# schematic.net
KiCad netlist of a schematic drawn in EAGLE
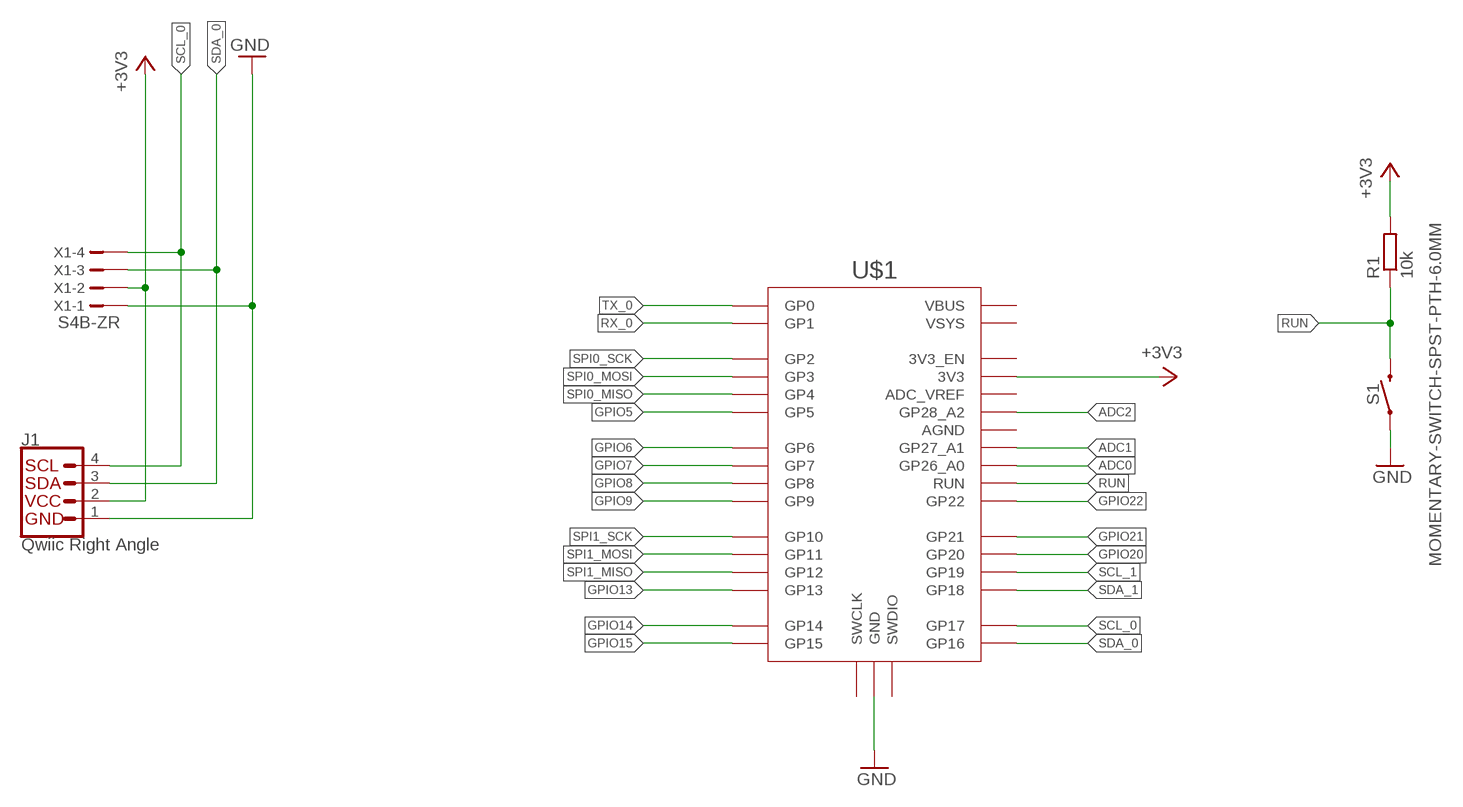
[diagram p0: schematic, sheet 1]

(export (version "E")
  (design (tool "Eeschema 10.0.6"))
  (components
    (comp (ref "J1")
      (value "Qwiic Right Angle")
      (footprint "eagle-import:JST04_1MM_RA")
      (libsource (lib "eagle-import") (part "I2C_STANDARDQWIIC"))
    )
    (comp (ref "R1")
      (value "10k")
      (footprint "eagle-import:0204_7")
      (libsource (lib "eagle-import") (part "R-EU_0204/7"))
    )
    (comp (ref "S1")
      (value "MOMENTARY-SWITCH-SPST-PTH-6.0MM")
      (footprint "eagle-import:TACTILE_SWITCH_PTH_6.0MM")
      (libsource (lib "eagle-import") (part "MOMENTARY-SWITCH-SPST-PTH-6.0MM"))
    )
    (comp (ref "U$1")
      (value "RPI_PICO-SMD")
      (footprint "eagle-import:RPI_PICO")
      (libsource (lib "eagle-import") (part "RPI_PICO-SMD"))
    )
    (comp (ref "X1")
      (value "S4B-ZR")
      (footprint "eagle-import:S4B-ZR")
      (fields (field (name "MF") "FARNELL") (field (name "MPN") "S4B-ZR(LF)(SN)"))
      (libsource (lib "eagle-import") (part "?4B-ZRS"))
    )
  )
  (nets
    (net (code "1") (name "+3V3") (class "Default")
      (node (ref "J1") (pin "2") (pinfunction "2_2") (pintype "power_in"))
      (node (ref "R1") (pin "2") (pinfunction "2_2") (pintype "passive"))
      (node (ref "U$1") (pin "3V3") (pinfunction "3V3_3V3") (pintype "bidirectional"))
      (node (ref "X1") (pin "2") (pinfunction "1_2") (pintype "passive"))
    )
    (net (code "2") (name "ADC0") (class "Default")
      (node (ref "U$1") (pin "GP26_A0") (pinfunction "GP26_A0_GP26_A0") (pintype "bidirectional"))
    )
    (net (code "3") (name "ADC1") (class "Default")
      (node (ref "U$1") (pin "GP27_A1") (pinfunction "GP27_A1_GP27_A1") (pintype "bidirectional"))
    )
    (net (code "4") (name "ADC2") (class "Default")
      (node (ref "U$1") (pin "GP28_A2") (pinfunction "GP28_A2_GP28_A2") (pintype "bidirectional"))
    )
    (net (code "5") (name "GND") (class "Default")
      (node (ref "J1") (pin "1") (pinfunction "1_1") (pintype "power_in"))
      (node (ref "S1") (pin "1") (pinfunction "1_1") (pintype "passive"))
      (node (ref "U$1") (pin "GND@1") (pinfunction "GND_GND@1") (pintype "bidirectional"))
      (node (ref "U$1") (pin "GND@2") (pinfunction "GND_GND@2") (pintype "bidirectional"))
      (node (ref "U$1") (pin "GND@3") (pinfunction "GND_GND@3") (pintype "bidirectional"))
      (node (ref "U$1") (pin "GND@4") (pinfunction "GND_GND@4") (pintype "bidirectional"))
      (node (ref "U$1") (pin "GND@5") (pinfunction "GND_GND@5") (pintype "bidirectional"))
      (node (ref "U$1") (pin "GND@6") (pinfunction "GND_GND@6") (pintype "bidirectional"))
      (node (ref "U$1") (pin "GND@7") (pinfunction "GND_GND@7") (pintype "bidirectional"))
      (node (ref "U$1") (pin "GND@8") (pinfunction "GND_GND@8") (pintype "bidirectional"))
      (node (ref "X1") (pin "1") (pinfunction "1_1") (pintype "passive"))
    )
    (net (code "6") (name "GPIO5") (class "Default")
      (node (ref "U$1") (pin "GP5") (pinfunction "GP5_GP5") (pintype "bidirectional"))
    )
    (net (code "7") (name "GPIO6") (class "Default")
      (node (ref "U$1") (pin "GP6") (pinfunction "GP6_GP6") (pintype "bidirectional"))
    )
    (net (code "8") (name "GPIO7") (class "Default")
      (node (ref "U$1") (pin "GP7") (pinfunction "GP7_GP7") (pintype "bidirectional"))
    )
    (net (code "9") (name "GPIO8") (class "Default")
      (node (ref "U$1") (pin "GP8") (pinfunction "GP8_GP8") (pintype "bidirectional"))
    )
    (net (code "10") (name "GPIO9") (class "Default")
      (node (ref "U$1") (pin "GP9") (pinfunction "GP9_GP9") (pintype "bidirectional"))
    )
    (net (code "11") (name "GPIO13") (class "Default")
      (node (ref "U$1") (pin "GP13") (pinfunction "GP13_GP13") (pintype "bidirectional"))
    )
    (net (code "12") (name "GPIO14") (class "Default")
      (node (ref "U$1") (pin "GP14") (pinfunction "GP14_GP14") (pintype "bidirectional"))
    )
    (net (code "13") (name "GPIO15") (class "Default")
      (node (ref "U$1") (pin "GP15") (pinfunction "GP15_GP15") (pintype "bidirectional"))
    )
    (net (code "14") (name "GPIO20") (class "Default")
      (node (ref "U$1") (pin "GP20") (pinfunction "GP20_GP20") (pintype "bidirectional"))
    )
    (net (code "15") (name "GPIO21") (class "Default")
      (node (ref "U$1") (pin "GP21") (pinfunction "GP21_GP21") (pintype "bidirectional"))
    )
    (net (code "16") (name "GPIO22") (class "Default")
      (node (ref "U$1") (pin "GP22") (pinfunction "GP22_GP22") (pintype "bidirectional"))
    )
    (net (code "17") (name "RUN") (class "Default")
      (node (ref "R1") (pin "1") (pinfunction "1_1") (pintype "passive"))
      (node (ref "S1") (pin "3") (pinfunction "2_3") (pintype "passive"))
      (node (ref "U$1") (pin "RUN") (pinfunction "RUN_RUN") (pintype "bidirectional"))
    )
    (net (code "18") (name "RX_0") (class "Default")
      (node (ref "U$1") (pin "GP1") (pinfunction "GP1_GP1") (pintype "bidirectional"))
    )
    (net (code "19") (name "SCL_0") (class "Default")
      (node (ref "J1") (pin "4") (pinfunction "4_4") (pintype "passive"))
      (node (ref "U$1") (pin "GP17") (pinfunction "GP17_GP17") (pintype "bidirectional"))
      (node (ref "X1") (pin "4") (pinfunction "1_4") (pintype "passive"))
    )
    (net (code "20") (name "SCL_1") (class "Default")
      (node (ref "U$1") (pin "GP19") (pinfunction "GP19_GP19") (pintype "bidirectional"))
    )
    (net (code "21") (name "SDA_0") (class "Default")
      (node (ref "J1") (pin "3") (pinfunction "3_3") (pintype "passive"))
      (node (ref "U$1") (pin "GP16") (pinfunction "GP16_GP16") (pintype "bidirectional"))
      (node (ref "X1") (pin "3") (pinfunction "1_3") (pintype "passive"))
    )
    (net (code "22") (name "SDA_1") (class "Default")
      (node (ref "U$1") (pin "GP18") (pinfunction "GP18_GP18") (pintype "bidirectional"))
    )
    (net (code "23") (name "SPI0_MISO") (class "Default")
      (node (ref "U$1") (pin "GP4") (pinfunction "GP4_GP4") (pintype "bidirectional"))
    )
    (net (code "24") (name "SPI0_MOSI") (class "Default")
      (node (ref "U$1") (pin "GP3") (pinfunction "GP3_GP3") (pintype "bidirectional"))
    )
    (net (code "25") (name "SPI0_SCK") (class "Default")
      (node (ref "U$1") (pin "GP2") (pinfunction "GP2_GP2") (pintype "bidirectional"))
    )
    (net (code "26") (name "SPI1_MISO") (class "Default")
      (node (ref "U$1") (pin "GP12") (pinfunction "GP12_GP12") (pintype "bidirectional"))
    )
    (net (code "27") (name "SPI1_MOSI") (class "Default")
      (node (ref "U$1") (pin "GP11") (pinfunction "GP11_GP11") (pintype "bidirectional"))
    )
    (net (code "28") (name "SPI1_SCK") (class "Default")
      (node (ref "U$1") (pin "GP10") (pinfunction "GP10_GP10") (pintype "bidirectional"))
    )
    (net (code "29") (name "TX_0") (class "Default")
      (node (ref "U$1") (pin "GP0") (pinfunction "GP0_GP0") (pintype "bidirectional"))
    )
    (net (code "30") (name "unconnected-(U$1-Pad3V3_EN)") (class "Default")
      (node (ref "U$1") (pin "3V3_EN") (pinfunction "3V3_EN_3V3_EN") (pintype "bidirectional"))
    )
    (net (code "31") (name "unconnected-(U$1-PadADC_VREF)") (class "Default")
      (node (ref "U$1") (pin "ADC_VREF") (pinfunction "ADC_VREF_ADC_VREF") (pintype "bidirectional"))
    )
    (net (code "32") (name "unconnected-(U$1-PadAGND)") (class "Default")
      (node (ref "U$1") (pin "AGND") (pinfunction "AGND_AGND") (pintype "bidirectional"))
    )
    (net (code "33") (name "unconnected-(U$1-PadSWCLK)") (class "Default")
      (node (ref "U$1") (pin "SWCLK") (pinfunction "SWCLK_SWCLK") (pintype "bidirectional"))
    )
    (net (code "34") (name "unconnected-(U$1-PadSWDIO)") (class "Default")
      (node (ref "U$1") (pin "SWDIO") (pinfunction "SWDIO_SWDIO") (pintype "bidirectional"))
    )
    (net (code "35") (name "unconnected-(U$1-PadVBUS)") (class "Default")
      (node (ref "U$1") (pin "VBUS") (pinfunction "VBUS_VBUS") (pintype "bidirectional"))
    )
    (net (code "36") (name "unconnected-(U$1-PadVSYS)") (class "Default")
      (node (ref "U$1") (pin "VSYS") (pinfunction "VSYS_VSYS") (pintype "bidirectional"))
    )
  )
)
